# AR1.net
KiCad netlist of a schematic drawn in EAGLE
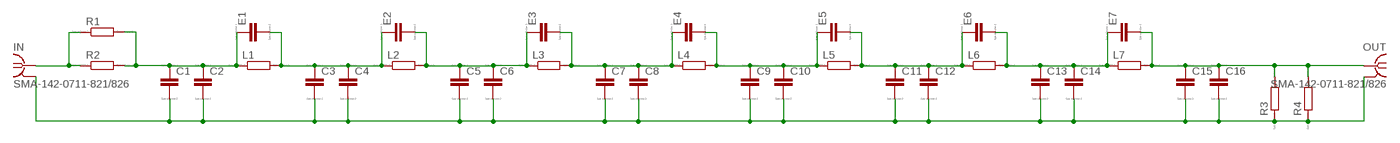
[diagram p0: schematic, sheet 1, overview]
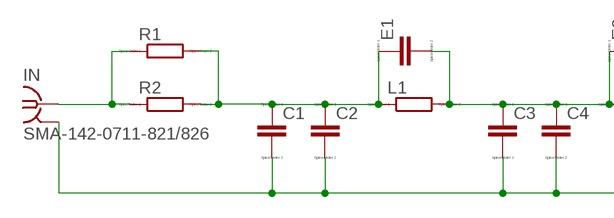
[diagram p1: schematic, sheet 1, part 1 of 4]
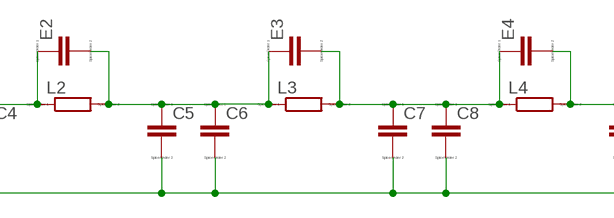
[diagram p2: schematic, sheet 1, part 2 of 4]
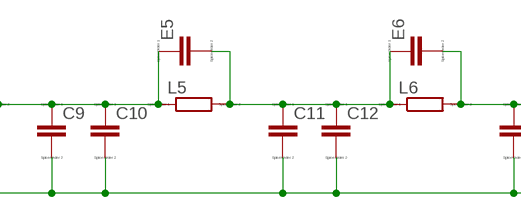
[diagram p3: schematic, sheet 1, part 3 of 4]
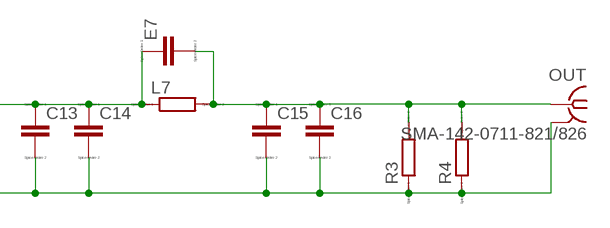
[diagram p4: schematic, sheet 1, part 4 of 4]

(export (version "E")
  (design (tool "Eeschema 10.0.6"))
  (components
    (comp (ref "C1") (value "C") (footprint "eagle-import:C0805") (libsource (lib "eagle-import") (part "C")))
    (comp (ref "C2") (value "C") (footprint "eagle-import:C0805") (libsource (lib "eagle-import") (part "C")))
    (comp (ref "C3") (value "C") (footprint "eagle-import:C0805") (libsource (lib "eagle-import") (part "C")))
    (comp (ref "C4") (value "C") (footprint "eagle-import:C0805") (libsource (lib "eagle-import") (part "C")))
    (comp (ref "C5") (value "C") (footprint "eagle-import:C0805") (libsource (lib "eagle-import") (part "C")))
    (comp (ref "C6") (value "C") (footprint "eagle-import:C0805") (libsource (lib "eagle-import") (part "C")))
    (comp (ref "C7") (value "C") (footprint "eagle-import:C0805") (libsource (lib "eagle-import") (part "C")))
    (comp (ref "C8") (value "C") (footprint "eagle-import:C0805") (libsource (lib "eagle-import") (part "C")))
    (comp (ref "C9") (value "C") (footprint "eagle-import:C0805") (libsource (lib "eagle-import") (part "C")))
    (comp (ref "C10")
      (value "C")
      (footprint "eagle-import:C0805")
      (libsource (lib "eagle-import") (part "C"))
    )
    (comp (ref "C11")
      (value "C")
      (footprint "eagle-import:C0805")
      (libsource (lib "eagle-import") (part "C"))
    )
    (comp (ref "C12")
      (value "C")
      (footprint "eagle-import:C0805")
      (libsource (lib "eagle-import") (part "C"))
    )
    (comp (ref "C13")
      (value "C")
      (footprint "eagle-import:C0805")
      (libsource (lib "eagle-import") (part "C"))
    )
    (comp (ref "C14")
      (value "C")
      (footprint "eagle-import:C0805")
      (libsource (lib "eagle-import") (part "C"))
    )
    (comp (ref "C15")
      (value "C")
      (footprint "eagle-import:C0805")
      (libsource (lib "eagle-import") (part "C"))
    )
    (comp (ref "C16")
      (value "C")
      (footprint "eagle-import:C0805")
      (libsource (lib "eagle-import") (part "C"))
    )
    (comp (ref "E1") (value "C") (footprint "eagle-import:C0805") (libsource (lib "eagle-import") (part "C")))
    (comp (ref "E2") (value "C") (footprint "eagle-import:C0805") (libsource (lib "eagle-import") (part "C")))
    (comp (ref "E3") (value "C") (footprint "eagle-import:C0805") (libsource (lib "eagle-import") (part "C")))
    (comp (ref "E4") (value "C") (footprint "eagle-import:C0805") (libsource (lib "eagle-import") (part "C")))
    (comp (ref "E5") (value "C") (footprint "eagle-import:C0805") (libsource (lib "eagle-import") (part "C")))
    (comp (ref "E6") (value "C") (footprint "eagle-import:C0805") (libsource (lib "eagle-import") (part "C")))
    (comp (ref "E7") (value "C") (footprint "eagle-import:C0805") (libsource (lib "eagle-import") (part "C")))
    (comp (ref "IN")
      (value "SMA-142-0711-821/826")
      (footprint "eagle-import:J502-ND-142-0711-821_826")
      (fields (field (name "MF") "JOHNSON COMPONENTS") (field (name "MPN") "142-0711-821"))
      (libsource (lib "eagle-import") (part "SMA-142-0711-821/826"))
    )
    (comp (ref "L1") (value "R") (footprint "eagle-import:R0805") (libsource (lib "eagle-import") (part "R")))
    (comp (ref "L2") (value "R") (footprint "eagle-import:R0805") (libsource (lib "eagle-import") (part "R")))
    (comp (ref "L3") (value "R") (footprint "eagle-import:R0805") (libsource (lib "eagle-import") (part "R")))
    (comp (ref "L4") (value "R") (footprint "eagle-import:R0805") (libsource (lib "eagle-import") (part "R")))
    (comp (ref "L5") (value "R") (footprint "eagle-import:R0805") (libsource (lib "eagle-import") (part "R")))
    (comp (ref "L6") (value "R") (footprint "eagle-import:R0805") (libsource (lib "eagle-import") (part "R")))
    (comp (ref "L7") (value "R") (footprint "eagle-import:R0805") (libsource (lib "eagle-import") (part "R")))
    (comp (ref "OUT")
      (value "SMA-142-0711-821/826")
      (footprint "eagle-import:J502-ND-142-0711-821_826")
      (fields (field (name "MF") "JOHNSON COMPONENTS") (field (name "MPN") "142-0711-821"))
      (libsource (lib "eagle-import") (part "SMA-142-0711-821/826"))
    )
    (comp (ref "R1") (value "R") (footprint "eagle-import:R0805") (libsource (lib "eagle-import") (part "R")))
    (comp (ref "R2") (value "R") (footprint "eagle-import:R0805") (libsource (lib "eagle-import") (part "R")))
    (comp (ref "R3") (value "R") (footprint "eagle-import:R0805") (libsource (lib "eagle-import") (part "R")))
    (comp (ref "R4") (value "R") (footprint "eagle-import:R0805") (libsource (lib "eagle-import") (part "R")))
  )
  (nets
    (net (code "1") (name "Net-(C1-Pad1)") (class "Default")
      (node (ref "C1") (pin "1") (pinfunction "1_1") (pintype "passive"))
      (node (ref "C2") (pin "1") (pinfunction "1_1") (pintype "passive"))
      (node (ref "E1") (pin "1") (pinfunction "1_1") (pintype "passive"))
      (node (ref "L1") (pin "1") (pinfunction "1_1") (pintype "passive"))
      (node (ref "R1") (pin "2") (pinfunction "2_2") (pintype "passive"))
      (node (ref "R2") (pin "2") (pinfunction "2_2") (pintype "passive"))
    )
    (net (code "2") (name "Net-(C1-Pad2)") (class "Default")
      (node (ref "C1") (pin "2") (pinfunction "2_2") (pintype "passive"))
      (node (ref "C10") (pin "2") (pinfunction "2_2") (pintype "passive"))
      (node (ref "C11") (pin "2") (pinfunction "2_2") (pintype "passive"))
      (node (ref "C12") (pin "2") (pinfunction "2_2") (pintype "passive"))
      (node (ref "C13") (pin "2") (pinfunction "2_2") (pintype "passive"))
      (node (ref "C14") (pin "2") (pinfunction "2_2") (pintype "passive"))
      (node (ref "C15") (pin "2") (pinfunction "2_2") (pintype "passive"))
      (node (ref "C16") (pin "2") (pinfunction "2_2") (pintype "passive"))
      (node (ref "C2") (pin "2") (pinfunction "2_2") (pintype "passive"))
      (node (ref "C3") (pin "2") (pinfunction "2_2") (pintype "passive"))
      (node (ref "C4") (pin "2") (pinfunction "2_2") (pintype "passive"))
      (node (ref "C5") (pin "2") (pinfunction "2_2") (pintype "passive"))
      (node (ref "C6") (pin "2") (pinfunction "2_2") (pintype "passive"))
      (node (ref "C7") (pin "2") (pinfunction "2_2") (pintype "passive"))
      (node (ref "C8") (pin "2") (pinfunction "2_2") (pintype "passive"))
      (node (ref "C9") (pin "2") (pinfunction "2_2") (pintype "passive"))
      (node (ref "IN") (pin "G@1") (pinfunction "2_G@1") (pintype "passive"))
      (node (ref "IN") (pin "G@2") (pinfunction "2_G@2") (pintype "passive"))
      (node (ref "IN") (pin "G@3") (pinfunction "2_G@3") (pintype "passive"))
      (node (ref "IN") (pin "G@4") (pinfunction "2_G@4") (pintype "passive"))
      (node (ref "OUT") (pin "G@1") (pinfunction "2_G@1") (pintype "passive"))
      (node (ref "OUT") (pin "G@2") (pinfunction "2_G@2") (pintype "passive"))
      (node (ref "OUT") (pin "G@3") (pinfunction "2_G@3") (pintype "passive"))
      (node (ref "OUT") (pin "G@4") (pinfunction "2_G@4") (pintype "passive"))
      (node (ref "R3") (pin "1") (pinfunction "1_1") (pintype "passive"))
      (node (ref "R4") (pin "1") (pinfunction "1_1") (pintype "passive"))
    )
    (net (code "3") (name "Net-(C3-Pad1)") (class "Default")
      (node (ref "C3") (pin "1") (pinfunction "1_1") (pintype "passive"))
      (node (ref "C4") (pin "1") (pinfunction "1_1") (pintype "passive"))
      (node (ref "E1") (pin "2") (pinfunction "2_2") (pintype "passive"))
      (node (ref "E2") (pin "1") (pinfunction "1_1") (pintype "passive"))
      (node (ref "L1") (pin "2") (pinfunction "2_2") (pintype "passive"))
      (node (ref "L2") (pin "1") (pinfunction "1_1") (pintype "passive"))
    )
    (net (code "4") (name "Net-(C5-Pad1)") (class "Default")
      (node (ref "C5") (pin "1") (pinfunction "1_1") (pintype "passive"))
      (node (ref "C6") (pin "1") (pinfunction "1_1") (pintype "passive"))
      (node (ref "E2") (pin "2") (pinfunction "2_2") (pintype "passive"))
      (node (ref "E3") (pin "1") (pinfunction "1_1") (pintype "passive"))
      (node (ref "L2") (pin "2") (pinfunction "2_2") (pintype "passive"))
      (node (ref "L3") (pin "1") (pinfunction "1_1") (pintype "passive"))
    )
    (net (code "5") (name "Net-(C7-Pad1)") (class "Default")
      (node (ref "C7") (pin "1") (pinfunction "1_1") (pintype "passive"))
      (node (ref "C8") (pin "1") (pinfunction "1_1") (pintype "passive"))
      (node (ref "E3") (pin "2") (pinfunction "2_2") (pintype "passive"))
      (node (ref "E4") (pin "1") (pinfunction "1_1") (pintype "passive"))
      (node (ref "L3") (pin "2") (pinfunction "2_2") (pintype "passive"))
      (node (ref "L4") (pin "1") (pinfunction "1_1") (pintype "passive"))
    )
    (net (code "6") (name "Net-(C10-Pad1)") (class "Default")
      (node (ref "C10") (pin "1") (pinfunction "1_1") (pintype "passive"))
      (node (ref "C9") (pin "1") (pinfunction "1_1") (pintype "passive"))
      (node (ref "E4") (pin "2") (pinfunction "2_2") (pintype "passive"))
      (node (ref "E5") (pin "1") (pinfunction "1_1") (pintype "passive"))
      (node (ref "L4") (pin "2") (pinfunction "2_2") (pintype "passive"))
      (node (ref "L5") (pin "1") (pinfunction "1_1") (pintype "passive"))
    )
    (net (code "7") (name "Net-(C11-Pad1)") (class "Default")
      (node (ref "C11") (pin "1") (pinfunction "1_1") (pintype "passive"))
      (node (ref "C12") (pin "1") (pinfunction "1_1") (pintype "passive"))
      (node (ref "E5") (pin "2") (pinfunction "2_2") (pintype "passive"))
      (node (ref "E6") (pin "1") (pinfunction "1_1") (pintype "passive"))
      (node (ref "L5") (pin "2") (pinfunction "2_2") (pintype "passive"))
      (node (ref "L6") (pin "1") (pinfunction "1_1") (pintype "passive"))
    )
    (net (code "8") (name "Net-(C13-Pad1)") (class "Default")
      (node (ref "C13") (pin "1") (pinfunction "1_1") (pintype "passive"))
      (node (ref "C14") (pin "1") (pinfunction "1_1") (pintype "passive"))
      (node (ref "E6") (pin "2") (pinfunction "2_2") (pintype "passive"))
      (node (ref "E7") (pin "1") (pinfunction "1_1") (pintype "passive"))
      (node (ref "L6") (pin "2") (pinfunction "2_2") (pintype "passive"))
      (node (ref "L7") (pin "1") (pinfunction "1_1") (pintype "passive"))
    )
    (net (code "9") (name "Net-(C15-Pad1)") (class "Default")
      (node (ref "C15") (pin "1") (pinfunction "1_1") (pintype "passive"))
      (node (ref "C16") (pin "1") (pinfunction "1_1") (pintype "passive"))
      (node (ref "E7") (pin "2") (pinfunction "2_2") (pintype "passive"))
      (node (ref "L7") (pin "2") (pinfunction "2_2") (pintype "passive"))
      (node (ref "OUT") (pin "1") (pinfunction "1_1") (pintype "passive"))
      (node (ref "R3") (pin "2") (pinfunction "2_2") (pintype "passive"))
      (node (ref "R4") (pin "2") (pinfunction "2_2") (pintype "passive"))
    )
    (net (code "10") (name "Net-(IN-Pad1)") (class "Default")
      (node (ref "IN") (pin "1") (pinfunction "1_1") (pintype "passive"))
      (node (ref "R1") (pin "1") (pinfunction "1_1") (pintype "passive"))
      (node (ref "R2") (pin "1") (pinfunction "1_1") (pintype "passive"))
    )
  )
)
